# Current_Measurement.net
KiCad netlist of a schematic drawn in Altium Designer
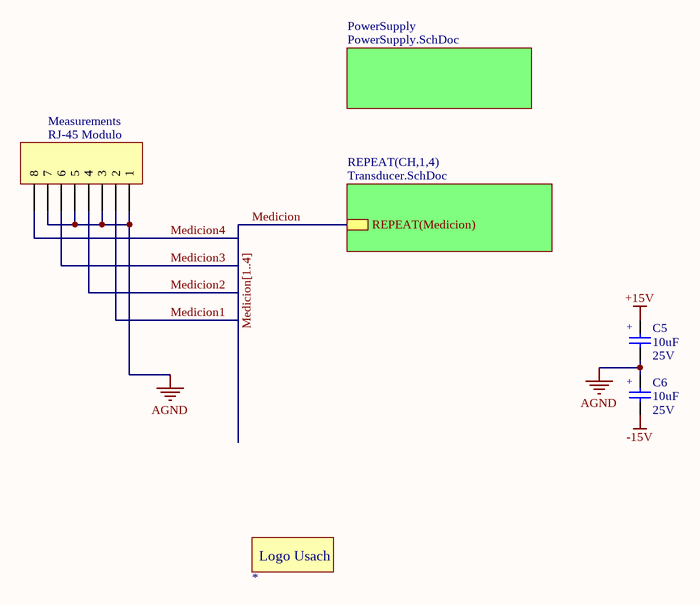
[diagram p0: Current Measurement.SchDoc]

(export (version "E")
  (design (tool "Eeschema 10.0.6"))
  (components
    (comp (ref "*")
      (value "LOGO USACH")
      (footprint "Logo Usach")
      (libsource (lib "Componentes_SOC") (part "LOGO USACH"))
    )
    (comp (ref "C5")
      (value "10uF")
      (footprint "CAP_1206 Tantalio")
      (description "Capacitor Tantalio")
      (fields (field (name "VOLTAGE") "25V"))
      (libsource (lib "Componentes_SOC") (part "Cap Tantalio 1206"))
    )
    (comp (ref "C6")
      (value "10uF")
      (footprint "CAP_1206 Tantalio")
      (description "Capacitor Tantalio")
      (fields (field (name "VOLTAGE") "25V"))
      (libsource (lib "Componentes_SOC") (part "Cap Tantalio 1206"))
    )
    (comp (ref "Measurements")
      (value "RJ-45 Modulo")
      (footprint "RJ45 1 Modulo SMD")
      (description "Modulo RJ-45 vertical SMD")
      (fields (field (name "PUBLISHER") "Altium Limited"))
      (libsource (lib "Componentes_SOC") (part "RJ45 1 modulo SMD"))
    )
  )
  (nets
    (net (code "1") (name "+15V") (class "Default")
      (node (ref "C5") (pin "1") (pinfunction "1_1") (pintype "passive"))
    )
    (net (code "2") (name "-15V") (class "Default")
      (node (ref "C6") (pin "2") (pinfunction "2_2") (pintype "passive"))
    )
    (net (code "4") (name "/Medicion1") (class "Default")
      (node (ref "Measurements") (pin "2") (pinfunction "2_2") (pintype "passive"))
    )
    (net (code "5") (name "/Medicion2") (class "Default")
      (node (ref "Measurements") (pin "4") (pinfunction "4_4") (pintype "passive"))
    )
    (net (code "6") (name "/Medicion3") (class "Default")
      (node (ref "Measurements") (pin "6") (pinfunction "6_6") (pintype "passive"))
    )
    (net (code "7") (name "/Medicion4") (class "Default")
      (node (ref "Measurements") (pin "8") (pinfunction "8_8") (pintype "passive"))
    )
    (net (code "9") (name "AGND") (class "Default")
      (node (ref "C5") (pin "2") (pinfunction "2_2") (pintype "passive"))
      (node (ref "C6") (pin "1") (pinfunction "1_1") (pintype "passive"))
      (node (ref "Measurements") (pin "1") (pinfunction "1_1") (pintype "passive"))
      (node (ref "Measurements") (pin "3") (pinfunction "3_3") (pintype "passive"))
      (node (ref "Measurements") (pin "5") (pinfunction "5_5") (pintype "passive"))
      (node (ref "Measurements") (pin "7") (pinfunction "7_7") (pintype "passive"))
    )
  )
)
